# AUDIO_EAR.net
KiCad netlist of a schematic drawn in Altium Designer
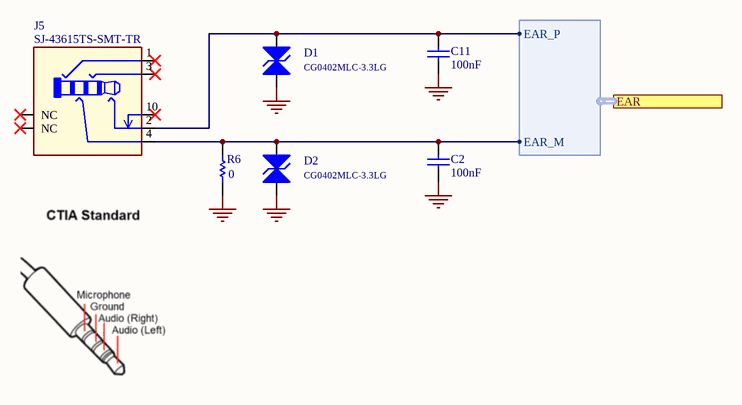
[diagram p0: AUDIO_EAR.SchDoc]

(export (version "E")
  (design (tool "Eeschema 10.0.6"))
  (components
    (comp (ref "C2")
      (value "100nF")
      (footprint "CAP-0402")
      (description "CAP CHIP 0402 100nF 10% 50V X5R")
      (fields (field (name "MANUFACTURER") "Murata") (field (name "PART NUMBER") "GRM155R61H104KE19D"))
      (libsource (lib "Clean") (part "CAP"))
    )
    (comp (ref "C11")
      (value "100nF")
      (footprint "CAP-0402")
      (description "CAP CHIP 0402 100nF 10% 50V X5R")
      (fields (field (name "MANUFACTURER") "Murata") (field (name "PART NUMBER") "GRM155R61H104KE19D"))
      (libsource (lib "Clean") (part "CAP"))
    )
    (comp (ref "D1")
      (value "CG0402MLC-3.3LG")
      (footprint "0402")
      (description "DIODE TVS SMD 0402 3.3V ESD PROTECTION")
      (fields (field (name "MANUFACTURER") "Bourns"))
      (libsource (lib "Clean") (part "Diode Bidirectional"))
    )
    (comp (ref "D2")
      (value "CG0402MLC-3.3LG")
      (footprint "0402")
      (description "DIODE TVS SMD 0402 3.3V ESD PROTECTION")
      (fields (field (name "MANUFACTURER") "Bourns"))
      (libsource (lib "Clean") (part "Diode Bidirectional"))
    )
    (comp (ref "J5")
      (value "SJ-43615TS-SMT-TR")
      (footprint "SJ-43615TS-SMT-TR")
      (description "CONN Audio Jack 3.5mm, 4 conductor, tip switch, SMD mid mount")
      (fields (field (name "MANUFACTURER") "Same Sky"))
      (libsource (lib "Clean") (part "SJ-43615TS-SMT-TR-Symbol-1"))
    )
    (comp (ref "R6")
      (value "0")
      (footprint "RES-0402")
      (description "RES CHIP 0402 0R 1/16W")
      (fields (field (name "POWER") "62.5mW") (field (name "MANUFACTURER") "Vishay"))
      (libsource (lib "Clean") (part "RES"))
    )
  )
  (nets
    (net (code "3") (name "GND") (class "Default")
      (node (ref "C11") (pin "1") (pinfunction "1_1") (pintype "passive"))
      (node (ref "C2") (pin "1") (pinfunction "1_1") (pintype "passive"))
      (node (ref "D1") (pin "A") (pinfunction "A_A") (pintype "passive"))
      (node (ref "D2") (pin "A") (pinfunction "A_A") (pintype "passive"))
      (node (ref "R6") (pin "1") (pinfunction "1_1") (pintype "passive"))
    )
    (net (code "4") (name "Net-(C2-Pad2)") (class "Default")
      (node (ref "C2") (pin "2") (pinfunction "2_2") (pintype "passive"))
      (node (ref "D2") (pin "C") (pinfunction "C_C") (pintype "passive"))
      (node (ref "J5") (pin "4") (pinfunction "4_4") (pintype "passive"))
      (node (ref "R6") (pin "2") (pinfunction "2_2") (pintype "passive"))
    )
    (net (code "5") (name "Net-(C11-Pad2)") (class "Default")
      (node (ref "C11") (pin "2") (pinfunction "2_2") (pintype "passive"))
      (node (ref "D1") (pin "C") (pinfunction "C_C") (pintype "passive"))
      (node (ref "J5") (pin "2") (pinfunction "2_2") (pintype "passive"))
    )
    (net (code "6") (name "unconnected-(J5-NC-Pad11)") (class "Default")
      (node (ref "J5") (pin "11") (pinfunction "NC_11") (pintype "passive+no_connect"))
    )
    (net (code "7") (name "unconnected-(J5-NC-Pad12)") (class "Default")
      (node (ref "J5") (pin "12") (pinfunction "NC_12") (pintype "passive+no_connect"))
    )
    (net (code "8") (name "unconnected-(J5-Pad1)") (class "Default")
      (node (ref "J5") (pin "1") (pinfunction "1_1") (pintype "passive+no_connect"))
    )
    (net (code "9") (name "unconnected-(J5-Pad3)") (class "Default")
      (node (ref "J5") (pin "3") (pinfunction "3_3") (pintype "passive+no_connect"))
    )
    (net (code "10") (name "unconnected-(J5-Pad10)") (class "Default")
      (node (ref "J5") (pin "10") (pinfunction "10_10") (pintype "passive+no_connect"))
    )
  )
)
